# openSX70_ALADDIN_V397SEEED_20180210.net
KiCad netlist of a schematic drawn in EAGLE
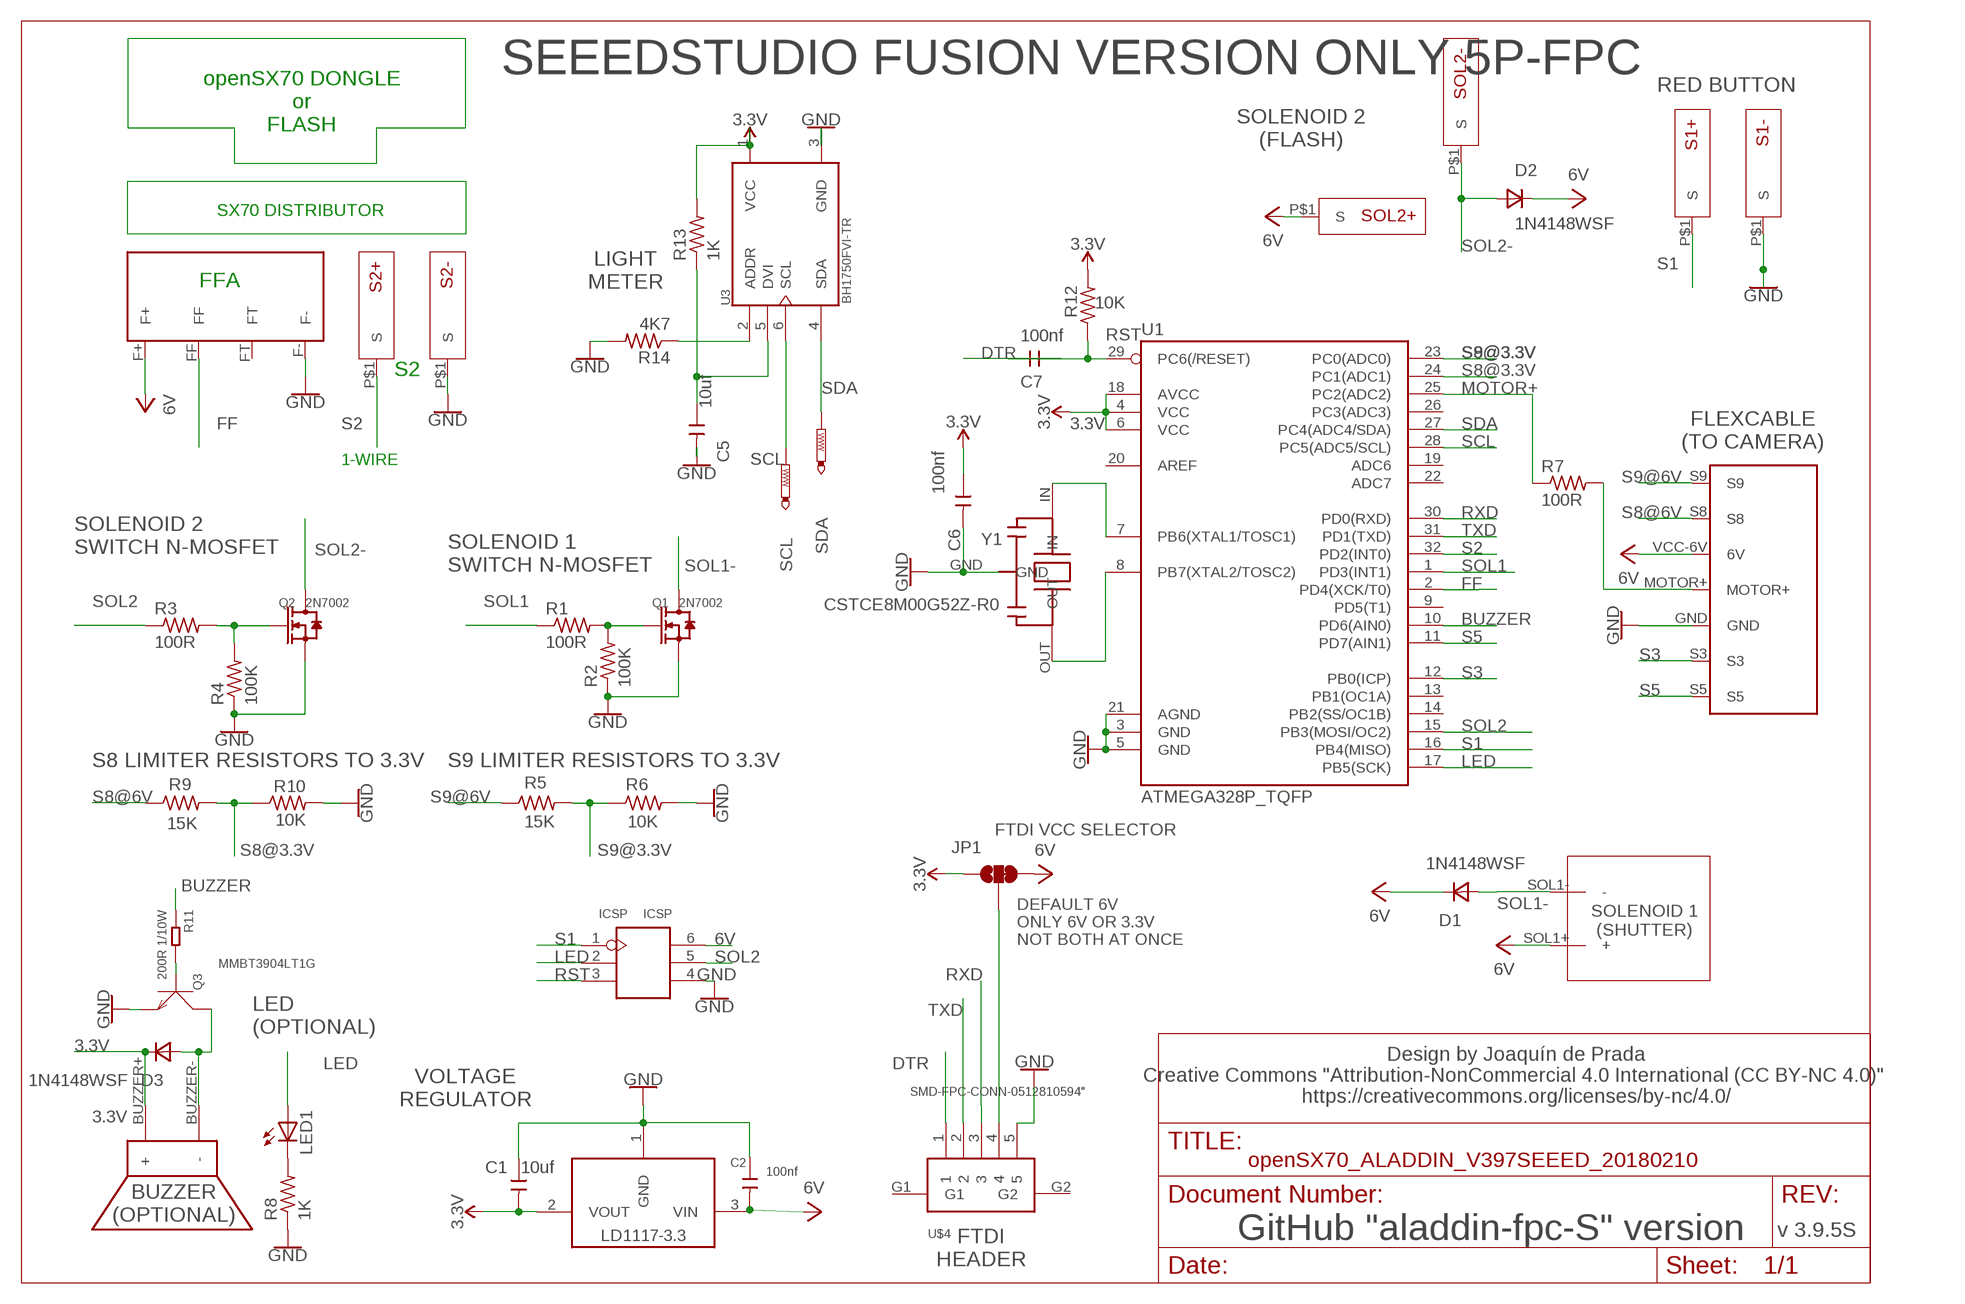
[diagram p0: schematic, sheet 1]

(export (version "E")
  (design (tool "Eeschema 10.0.6"))
  (components
    (comp (ref "C1")
      (value "10uf")
      (footprint "eagle-import:C0603")
      (fields (field (name "MPN") "CC0603KRX5R6BB106"))
      (libsource (lib "eagle-import") (part "CERAMIC-10UF-10V-10%-X5R(0603)"))
    )
    (comp (ref "C2")
      (value "100nf")
      (footprint "eagle-import:C0603")
      (fields (field (name "MPN") "CC0603KRX7R9BB104"))
      (libsource (lib "eagle-import") (part "CERAMIC-100NF-50V-10%-X7R(0603)"))
    )
    (comp (ref "C5")
      (value "10uf")
      (footprint "eagle-import:C0603")
      (fields (field (name "MPN") "CC0603KRX5R6BB106"))
      (libsource (lib "eagle-import") (part "CERAMIC-10UF-10V-10%-X5R(0603)"))
    )
    (comp (ref "C6")
      (value "100nf")
      (footprint "eagle-import:C0603")
      (fields (field (name "MPN") "CC0603KRX7R9BB104"))
      (libsource (lib "eagle-import") (part "CERAMIC-100NF-50V-10%-X7R(0603)"))
    )
    (comp (ref "C7")
      (value "100nf")
      (footprint "eagle-import:C0603")
      (fields (field (name "MPN") "CC0603KRX7R9BB104"))
      (libsource (lib "eagle-import") (part "CERAMIC-100NF-50V-10%-X7R(0603)"))
    )
    (comp (ref "D1")
      (value "1N4148WSF")
      (footprint "eagle-import:SOD323")
      (fields (field (name "MPN") "CDSOD323-T05C"))
      (libsource (lib "eagle-import") (part "DSOD323"))
    )
    (comp (ref "D2")
      (value "1N4148WSF")
      (footprint "eagle-import:SOD323")
      (fields (field (name "MPN") "CDSOD323-T05C"))
      (libsource (lib "eagle-import") (part "DSOD323"))
    )
    (comp (ref "D3")
      (value "1N4148WSF")
      (footprint "eagle-import:SOD323")
      (fields (field (name "MPN") "CDSOD323-T05C"))
      (libsource (lib "eagle-import") (part "DSOD323"))
    )
    (comp (ref "ICSP")
      (value "ICSP")
      (footprint "eagle-import:H2X3-2.54")
      (libsource (lib "eagle-import") (part "ICSP"))
    )
    (comp (ref "JP1")
      (value "FTDI VCC SELECTOR")
      (footprint "eagle-import:SMT-JUMPER_3_1-NC_TRACE_SILK")
      (libsource (lib "eagle-import") (part "JUMPER-SMT_3_1-NC_TRACE_SILK"))
    )
    (comp (ref "LD11172.5V")
      (value "LD1117 2.5V")
      (footprint "eagle-import:SOT223")
      (fields (field (name "MF") "Advanced Monolithic Systems") (field (name "MP") "AMS1117-5.0"))
      (libsource (lib "eagle-import") (part "LD1117-3.3"))
    )
    (comp (ref "LED1")
      (value "LEDCHIPLED_0805")
      (footprint "eagle-import:CHIPLED_0805")
      (libsource (lib "eagle-import") (part "LEDCHIPLED_0805"))
    )
    (comp (ref "Q1")
      (value "2N7002")
      (footprint "eagle-import:SOT-23")
      (fields (field (name "MPN") "2N7002,215"))
      (libsource (lib "eagle-import") (part "SMD-MOSFET-N-CH-60V-300MA-LOGIC-LEVEL-FET-2N7002(SOT-23)"))
    )
    (comp (ref "Q2")
      (value "2N7002")
      (footprint "eagle-import:SOT-23")
      (fields (field (name "MPN") "2N7002,215"))
      (libsource (lib "eagle-import") (part "SMD-MOSFET-N-CH-60V-300MA-LOGIC-LEVEL-FET-2N7002(SOT-23)"))
    )
    (comp (ref "Q3")
      (value "MMBT3904LT1G")
      (footprint "eagle-import:SOT-23")
      (libsource (lib "eagle-import") (part "SMD-TRANSISTORS-NPN-40V-200MA-MMBT3904LT1G(SOT-23)"))
    )
    (comp (ref "R1")
      (value "100R")
      (footprint "eagle-import:R0603")
      (libsource (lib "eagle-import") (part "R-US_R0603"))
    )
    (comp (ref "R2")
      (value "100K")
      (footprint "eagle-import:R0603")
      (libsource (lib "eagle-import") (part "R-US_R0603"))
    )
    (comp (ref "R3")
      (value "100R")
      (footprint "eagle-import:R0603")
      (libsource (lib "eagle-import") (part "R-US_R0603"))
    )
    (comp (ref "R4")
      (value "100K")
      (footprint "eagle-import:R0603")
      (libsource (lib "eagle-import") (part "R-US_R0603"))
    )
    (comp (ref "R5")
      (value "15K")
      (footprint "eagle-import:R0603")
      (libsource (lib "eagle-import") (part "R-US_R0603"))
    )
    (comp (ref "R6")
      (value "10K")
      (footprint "eagle-import:R0603")
      (libsource (lib "eagle-import") (part "R-US_R0603"))
    )
    (comp (ref "R7")
      (value "100R")
      (footprint "eagle-import:R0603")
      (libsource (lib "eagle-import") (part "R-US_R0603"))
    )
    (comp (ref "R8")
      (value "1K")
      (footprint "eagle-import:R0603")
      (libsource (lib "eagle-import") (part "R-US_R0603"))
    )
    (comp (ref "R9")
      (value "15K")
      (footprint "eagle-import:R0603")
      (libsource (lib "eagle-import") (part "R-US_R0603"))
    )
    (comp (ref "R10")
      (value "10K")
      (footprint "eagle-import:R0603")
      (libsource (lib "eagle-import") (part "R-US_R0603"))
    )
    (comp (ref "R11")
      (value "200R 1/10W")
      (footprint "eagle-import:R0603")
      (fields (field (name "MPN") "RC0603JR-07200RL"))
      (libsource (lib "eagle-import") (part "SMD-RES-200R-5%-1/10W(0603)"))
    )
    (comp (ref "R12")
      (value "10K")
      (footprint "eagle-import:R0603")
      (libsource (lib "eagle-import") (part "R-US_R0603"))
    )
    (comp (ref "R13")
      (value "1K")
      (footprint "eagle-import:R0603")
      (libsource (lib "eagle-import") (part "R-US_R0603"))
    )
    (comp (ref "R14")
      (value "4K7")
      (footprint "eagle-import:R0603")
      (libsource (lib "eagle-import") (part "R-US_R0603"))
    )
    (comp (ref "S1+")
      (value "SX70-S-PAD-NEW")
      (footprint "eagle-import:SX70-S-PAD2")
      (libsource (lib "eagle-import") (part "SX70-S-PAD-NEW"))
    )
    (comp (ref "S1-")
      (value "SX70-S-PAD-NEW")
      (footprint "eagle-import:SX70-S-PAD2")
      (libsource (lib "eagle-import") (part "SX70-S-PAD-NEW"))
    )
    (comp (ref "S2+")
      (value "SX70-S-PAD-NEW")
      (footprint "eagle-import:SX70-S-PAD2")
      (libsource (lib "eagle-import") (part "SX70-S-PAD-NEW"))
    )
    (comp (ref "S2-")
      (value "SX70-S-PAD-NEW")
      (footprint "eagle-import:SX70-S-PAD2")
      (libsource (lib "eagle-import") (part "SX70-S-PAD-NEW"))
    )
    (comp (ref "SCL")
      (value "PTR1TP08R")
      (footprint "eagle-import:TP08R")
      (libsource (lib "eagle-import") (part "PTR1TP08R"))
    )
    (comp (ref "SDA")
      (value "PTR1TP08R")
      (footprint "eagle-import:TP08R")
      (libsource (lib "eagle-import") (part "PTR1TP08R"))
    )
    (comp (ref "SOL1")
      (value "SX70-SOLENOID1-2PADS")
      (footprint "eagle-import:SX70-SOLENOID1-2")
      (libsource (lib "eagle-import") (part "SX70-SOLENOID1-2PADS"))
    )
    (comp (ref "SOL2+")
      (value "SX70-S-PAD-NEW")
      (footprint "eagle-import:SX70-S-PAD2")
      (libsource (lib "eagle-import") (part "SX70-S-PAD-NEW"))
    )
    (comp (ref "SOL2-")
      (value "SX70-S-PAD-NEW")
      (footprint "eagle-import:SX70-S-PAD2")
      (libsource (lib "eagle-import") (part "SX70-S-PAD-NEW"))
    )
    (comp (ref "U$1")
      (value "SX70-7-PAD")
      (footprint "eagle-import:SX70-7-PAD")
      (libsource (lib "eagle-import") (part "SX70-7-PAD"))
    )
    (comp (ref "U$2")
      (value "FFA")
      (footprint "eagle-import:FFA-PAD-PACKAGE")
      (libsource (lib "eagle-import") (part "SX70-FFA-PAD"))
    )
    (comp (ref "U$3")
      (value "CSET8-5G_V2")
      (footprint "eagle-import:CSET8-5G_PACKAGE")
      (libsource (lib "eagle-import") (part "CSET8-5G_V2"))
    )
    (comp (ref "U$4")
      (value "SMD-FPC-CONN-0512810594\"")
      (footprint "eagle-import:51281-0594")
      (libsource (lib "eagle-import") (part "SMD-FPC-CONN-0512810594{dblquote}"))
    )
    (comp (ref "U1")
      (value "ATMEGA328P_TQFP")
      (footprint "eagle-import:TQFP32-08")
      (libsource (lib "eagle-import") (part "ATMEGA328P_TQFP"))
    )
    (comp (ref "U3")
      (value "BH1750FVI-TR")
      (footprint "eagle-import:SOTFL50P300X75-6N")
      (fields (field (name "MF") "Rohm"))
      (libsource (lib "eagle-import") (part "BH1750FVI-TR"))
    )
    (comp (ref "Y1")
      (value "CSTCE8M00G52Z-R0")
      (footprint "eagle-import:CFP95P160X100-3N")
      (fields (field (name "MF") "Murata") (field (name "MP") "CSTCE16M0V53-R0"))
      (libsource (lib "eagle-import") (part "CSTCE16M0V53-R0"))
    )
  )
  (nets
    (net (code "1") (name "/BUZZER") (class "Default")
      (node (ref "R11") (pin "1") (pinfunction "1_1") (pintype "passive"))
      (node (ref "U1") (pin "10") (pinfunction "PD6(AIN0)_10") (pintype "bidirectional"))
    )
    (net (code "2") (name "/DTR") (class "Default")
      (node (ref "C7") (pin "1") (pinfunction "1_1") (pintype "passive"))
      (node (ref "U$4") (pin "1") (pinfunction "1_1") (pintype "bidirectional"))
    )
    (net (code "3") (name "/FF") (class "Default")
      (node (ref "U$2") (pin "FF") (pinfunction "FF_FF") (pintype "bidirectional"))
      (node (ref "U1") (pin "2") (pinfunction "PD4(XCK/T0)_2") (pintype "bidirectional"))
    )
    (net (code "4") (name "/LED") (class "Default")
      (node (ref "ICSP") (pin "2") (pinfunction "SCK_2") (pintype "bidirectional"))
      (node (ref "LED1") (pin "A") (pinfunction "A_A") (pintype "passive"))
      (node (ref "U1") (pin "17") (pinfunction "PB5(SCK)_17") (pintype "bidirectional"))
    )
    (net (code "5") (name "/MOTOR+") (class "Default")
      (node (ref "R7") (pin "1") (pinfunction "1_1") (pintype "passive"))
      (node (ref "U1") (pin "25") (pinfunction "PC2(ADC2)_25") (pintype "bidirectional"))
    )
    (net (code "6") (name "/RST") (class "Default")
      (node (ref "C7") (pin "2") (pinfunction "2_2") (pintype "passive"))
      (node (ref "ICSP") (pin "3") (pinfunction "RST_3") (pintype "bidirectional"))
      (node (ref "R12") (pin "1") (pinfunction "1_1") (pintype "passive"))
      (node (ref "U1") (pin "29") (pinfunction "PC6(/RESET)_29") (pintype "bidirectional"))
    )
    (net (code "7") (name "/RXD") (class "Default")
      (node (ref "U$4") (pin "3") (pinfunction "3_3") (pintype "bidirectional"))
      (node (ref "U1") (pin "30") (pinfunction "PD0(RXD)_30") (pintype "bidirectional"))
    )
    (net (code "8") (name "/S1") (class "Default")
      (node (ref "ICSP") (pin "1") (pinfunction "MISO_1") (pintype "bidirectional"))
      (node (ref "S1+") (pin "P$1") (pinfunction "S_P$1") (pintype "bidirectional"))
      (node (ref "U1") (pin "16") (pinfunction "PB4(MISO)_16") (pintype "bidirectional"))
    )
    (net (code "9") (name "/S2") (class "Default")
      (node (ref "S2+") (pin "P$1") (pinfunction "S_P$1") (pintype "bidirectional"))
      (node (ref "U1") (pin "32") (pinfunction "PD2(INT0)_32") (pintype "bidirectional"))
    )
    (net (code "10") (name "/S3") (class "Default")
      (node (ref "U$1") (pin "S3") (pinfunction "S3_S3") (pintype "bidirectional"))
      (node (ref "U1") (pin "12") (pinfunction "PB0(ICP)_12") (pintype "bidirectional"))
    )
    (net (code "11") (name "/S5") (class "Default")
      (node (ref "U$1") (pin "S5") (pinfunction "S5_S5") (pintype "bidirectional"))
      (node (ref "U1") (pin "11") (pinfunction "PD7(AIN1)_11") (pintype "bidirectional"))
    )
    (net (code "12") (name "/S8@3.3V") (class "Default")
      (node (ref "R10") (pin "1") (pinfunction "1_1") (pintype "passive"))
      (node (ref "R9") (pin "2") (pinfunction "2_2") (pintype "passive"))
      (node (ref "U1") (pin "24") (pinfunction "PC1(ADC1)_24") (pintype "bidirectional"))
    )
    (net (code "13") (name "/S8@6V") (class "Default")
      (node (ref "R9") (pin "1") (pinfunction "1_1") (pintype "passive"))
      (node (ref "U$1") (pin "S8") (pinfunction "S8_S8") (pintype "bidirectional"))
    )
    (net (code "14") (name "/S9@3.3V") (class "Default")
      (node (ref "R5") (pin "2") (pinfunction "2_2") (pintype "passive"))
      (node (ref "R6") (pin "1") (pinfunction "1_1") (pintype "passive"))
      (node (ref "U1") (pin "23") (pinfunction "PC0(ADC0)_23") (pintype "bidirectional"))
    )
    (net (code "15") (name "/S9@6V") (class "Default")
      (node (ref "R5") (pin "1") (pinfunction "1_1") (pintype "passive"))
      (node (ref "U$1") (pin "S9") (pinfunction "S9_S9") (pintype "bidirectional"))
    )
    (net (code "16") (name "/SCL") (class "Default")
      (node (ref "SCL") (pin "TP") (pinfunction "TP_TP") (pintype "input"))
      (node (ref "U1") (pin "28") (pinfunction "PC5(ADC5/SCL)_28") (pintype "bidirectional"))
      (node (ref "U3") (pin "6") (pinfunction "SCL_6") (pintype "input"))
    )
    (net (code "17") (name "/SDA") (class "Default")
      (node (ref "SDA") (pin "TP") (pinfunction "TP_TP") (pintype "input"))
      (node (ref "U1") (pin "27") (pinfunction "PC4(ADC4/SDA)_27") (pintype "bidirectional"))
      (node (ref "U3") (pin "4") (pinfunction "SDA_4") (pintype "bidirectional"))
    )
    (net (code "18") (name "/SOL1") (class "Default")
      (node (ref "R1") (pin "1") (pinfunction "1_1") (pintype "passive"))
      (node (ref "U1") (pin "1") (pinfunction "PD3(INT1)_1") (pintype "bidirectional"))
    )
    (net (code "19") (name "/SOL1-") (class "Default")
      (node (ref "D1") (pin "2") (pinfunction "A_2") (pintype "passive"))
      (node (ref "Q1") (pin "3") (pinfunction "D_3") (pintype "passive"))
      (node (ref "SOL1") (pin "SOL1-") (pinfunction "-_SOL1-") (pintype "bidirectional"))
    )
    (net (code "20") (name "/SOL2") (class "Default")
      (node (ref "ICSP") (pin "5") (pinfunction "MOSI_5") (pintype "bidirectional"))
      (node (ref "R3") (pin "1") (pinfunction "1_1") (pintype "passive"))
      (node (ref "U1") (pin "15") (pinfunction "PB3(MOSI/OC2)_15") (pintype "bidirectional"))
    )
    (net (code "21") (name "/SOL2-") (class "Default")
      (node (ref "D2") (pin "2") (pinfunction "A_2") (pintype "passive"))
      (node (ref "Q2") (pin "3") (pinfunction "D_3") (pintype "passive"))
      (node (ref "SOL2-") (pin "P$1") (pinfunction "S_P$1") (pintype "bidirectional"))
    )
    (net (code "22") (name "/TXD") (class "Default")
      (node (ref "U$4") (pin "2") (pinfunction "2_2") (pintype "bidirectional"))
      (node (ref "U1") (pin "31") (pinfunction "PD1(TXD)_31") (pintype "bidirectional"))
    )
    (net (code "23") (name "3.3V") (class "Default")
      (node (ref "C1") (pin "2") (pinfunction "2_2") (pintype "passive"))
      (node (ref "C6") (pin "1") (pinfunction "1_1") (pintype "passive"))
      (node (ref "D3") (pin "1") (pinfunction "C_1") (pintype "passive"))
      (node (ref "JP1") (pin "1") (pinfunction "1_1") (pintype "passive"))
      (node (ref "LD11172.5V") (pin "2") (pinfunction "VOUT_2") (pintype "bidirectional"))
      (node (ref "R12") (pin "2") (pinfunction "2_2") (pintype "passive"))
      (node (ref "R13") (pin "2") (pinfunction "2_2") (pintype "passive"))
      (node (ref "U$3") (pin "BUZZER+") (pinfunction "+_BUZZER+") (pintype "bidirectional"))
      (node (ref "U1") (pin "18") (pinfunction "AVCC_18") (pintype "bidirectional"))
      (node (ref "U1") (pin "4") (pinfunction "VCC_4") (pintype "bidirectional"))
      (node (ref "U1") (pin "6") (pinfunction "VCC_6") (pintype "bidirectional"))
      (node (ref "U3") (pin "1") (pinfunction "VCC_1") (pintype "power_in"))
    )
    (net (code "24") (name "6V") (class "Default")
      (node (ref "C2") (pin "2") (pinfunction "2_2") (pintype "passive"))
      (node (ref "D1") (pin "1") (pinfunction "C_1") (pintype "passive"))
      (node (ref "D2") (pin "1") (pinfunction "C_1") (pintype "passive"))
      (node (ref "ICSP") (pin "6") (pinfunction "VCC_6") (pintype "bidirectional"))
      (node (ref "JP1") (pin "3") (pinfunction "3_3") (pintype "passive"))
      (node (ref "LD11172.5V") (pin "3") (pinfunction "VIN_3") (pintype "bidirectional"))
      (node (ref "SOL1") (pin "SOL1+") (pinfunction "+_SOL1+") (pintype "bidirectional"))
      (node (ref "SOL2+") (pin "P$1") (pinfunction "S_P$1") (pintype "bidirectional"))
      (node (ref "U$1") (pin "VCC-6V") (pinfunction "6V_VCC-6V") (pintype "bidirectional"))
      (node (ref "U$2") (pin "F+") (pinfunction "F+_F+") (pintype "bidirectional"))
    )
    (net (code "25") (name "GND") (class "Default")
      (node (ref "C1") (pin "1") (pinfunction "1_1") (pintype "passive"))
      (node (ref "C2") (pin "1") (pinfunction "1_1") (pintype "passive"))
      (node (ref "C5") (pin "2") (pinfunction "2_2") (pintype "passive"))
      (node (ref "C6") (pin "2") (pinfunction "2_2") (pintype "passive"))
      (node (ref "ICSP") (pin "4") (pinfunction "GND_4") (pintype "bidirectional"))
      (node (ref "LD11172.5V") (pin "1") (pinfunction "GND_1") (pintype "bidirectional"))
      (node (ref "Q1") (pin "2") (pinfunction "S_2") (pintype "passive"))
      (node (ref "Q2") (pin "2") (pinfunction "S_2") (pintype "passive"))
      (node (ref "Q3") (pin "2") (pinfunction "E_2") (pintype "passive"))
      (node (ref "R10") (pin "2") (pinfunction "2_2") (pintype "passive"))
      (node (ref "R14") (pin "2") (pinfunction "2_2") (pintype "passive"))
      (node (ref "R2") (pin "1") (pinfunction "1_1") (pintype "passive"))
      (node (ref "R4") (pin "1") (pinfunction "1_1") (pintype "passive"))
      (node (ref "R6") (pin "2") (pinfunction "2_2") (pintype "passive"))
      (node (ref "R8") (pin "1") (pinfunction "1_1") (pintype "passive"))
      (node (ref "S1-") (pin "P$1") (pinfunction "S_P$1") (pintype "bidirectional"))
      (node (ref "S2-") (pin "P$1") (pinfunction "S_P$1") (pintype "bidirectional"))
      (node (ref "U$1") (pin "GND") (pinfunction "GND_GND") (pintype "bidirectional"))
      (node (ref "U$2") (pin "F-") (pinfunction "F-_F-") (pintype "bidirectional"))
      (node (ref "U$4") (pin "5") (pinfunction "5_5") (pintype "bidirectional"))
      (node (ref "U1") (pin "21") (pinfunction "AGND_21") (pintype "bidirectional"))
      (node (ref "U1") (pin "3") (pinfunction "GND_3") (pintype "bidirectional"))
      (node (ref "U1") (pin "5") (pinfunction "GND_5") (pintype "bidirectional"))
      (node (ref "U3") (pin "3") (pinfunction "GND_3") (pintype "power_in"))
      (node (ref "Y1") (pin "GND") (pinfunction "GND_GND") (pintype "passive"))
    )
    (net (code "26") (name "Net-(D3-A)") (class "Default")
      (node (ref "D3") (pin "2") (pinfunction "A_2") (pintype "passive"))
      (node (ref "Q3") (pin "3") (pinfunction "C_3") (pintype "passive"))
      (node (ref "U$3") (pin "BUZZER-") (pinfunction "-_BUZZER-") (pintype "bidirectional"))
    )
    (net (code "27") (name "Net-(JP1-Pad2)") (class "Default")
      (node (ref "JP1") (pin "2") (pinfunction "2_2") (pintype "passive"))
      (node (ref "U$4") (pin "4") (pinfunction "4_4") (pintype "bidirectional"))
    )
    (net (code "28") (name "Net-(LED1-PadC)") (class "Default")
      (node (ref "LED1") (pin "C") (pinfunction "C_C") (pintype "passive"))
      (node (ref "R8") (pin "2") (pinfunction "2_2") (pintype "passive"))
    )
    (net (code "29") (name "Net-(Q1-G)") (class "Default")
      (node (ref "Q1") (pin "1") (pinfunction "G_1") (pintype "passive"))
      (node (ref "R1") (pin "2") (pinfunction "2_2") (pintype "passive"))
      (node (ref "R2") (pin "2") (pinfunction "2_2") (pintype "passive"))
    )
    (net (code "30") (name "Net-(Q2-G)") (class "Default")
      (node (ref "Q2") (pin "1") (pinfunction "G_1") (pintype "passive"))
      (node (ref "R3") (pin "2") (pinfunction "2_2") (pintype "passive"))
      (node (ref "R4") (pin "2") (pinfunction "2_2") (pintype "passive"))
    )
    (net (code "31") (name "Net-(Q3-B)") (class "Default")
      (node (ref "Q3") (pin "1") (pinfunction "B_1") (pintype "passive"))
      (node (ref "R11") (pin "2") (pinfunction "2_2") (pintype "passive"))
    )
    (net (code "32") (name "Net-(R7-Pad2)") (class "Default")
      (node (ref "R7") (pin "2") (pinfunction "2_2") (pintype "passive"))
      (node (ref "U$1") (pin "MOTOR+") (pinfunction "MOTOR+_MOTOR+") (pintype "bidirectional"))
    )
    (net (code "33") (name "Net-(U1-PB6(XTAL1{slash}TOSC1))") (class "Default")
      (node (ref "U1") (pin "7") (pinfunction "PB6(XTAL1/TOSC1)_7") (pintype "bidirectional"))
      (node (ref "Y1") (pin "IN") (pinfunction "IN_IN") (pintype "input"))
    )
    (net (code "34") (name "Net-(U1-PB7(XTAL2{slash}TOSC2))") (class "Default")
      (node (ref "U1") (pin "8") (pinfunction "PB7(XTAL2/TOSC2)_8") (pintype "bidirectional"))
      (node (ref "Y1") (pin "OUT") (pinfunction "OUT_OUT") (pintype "output"))
    )
    (net (code "35") (name "Net-(U3-ADDR)") (class "Default")
      (node (ref "R14") (pin "1") (pinfunction "1_1") (pintype "passive"))
      (node (ref "U3") (pin "2") (pinfunction "ADDR_2") (pintype "input"))
    )
    (net (code "36") (name "Net-(U3-DVI)") (class "Default")
      (node (ref "C5") (pin "1") (pinfunction "1_1") (pintype "passive"))
      (node (ref "R13") (pin "1") (pinfunction "1_1") (pintype "passive"))
      (node (ref "U3") (pin "5") (pinfunction "DVI_5") (pintype "input"))
    )
    (net (code "37") (name "unconnected-(U$2-PadFT)") (class "Default")
      (node (ref "U$2") (pin "FT") (pinfunction "FT_FT") (pintype "bidirectional"))
    )
    (net (code "38") (name "unconnected-(U$4-PadG1)") (class "Default")
      (node (ref "U$4") (pin "G1") (pinfunction "G1_G1") (pintype "bidirectional"))
    )
    (net (code "39") (name "unconnected-(U$4-PadG2)") (class "Default")
      (node (ref "U$4") (pin "G2") (pinfunction "G2_G2") (pintype "bidirectional"))
    )
    (net (code "40") (name "unconnected-(U1-ADC6-Pad19)") (class "Default")
      (node (ref "U1") (pin "19") (pinfunction "ADC6_19") (pintype "bidirectional"))
    )
    (net (code "41") (name "unconnected-(U1-ADC7-Pad22)") (class "Default")
      (node (ref "U1") (pin "22") (pinfunction "ADC7_22") (pintype "bidirectional"))
    )
    (net (code "42") (name "unconnected-(U1-AREF-Pad20)") (class "Default")
      (node (ref "U1") (pin "20") (pinfunction "AREF_20") (pintype "bidirectional"))
    )
    (net (code "43") (name "unconnected-(U1-PB1(OC1A)-Pad13)") (class "Default")
      (node (ref "U1") (pin "13") (pinfunction "PB1(OC1A)_13") (pintype "bidirectional"))
    )
    (net (code "44") (name "unconnected-(U1-PB2(SS{slash}OC1B)-Pad14)") (class "Default")
      (node (ref "U1") (pin "14") (pinfunction "PB2(SS/OC1B)_14") (pintype "bidirectional"))
    )
    (net (code "45") (name "unconnected-(U1-PC3(ADC3)-Pad26)") (class "Default")
      (node (ref "U1") (pin "26") (pinfunction "PC3(ADC3)_26") (pintype "bidirectional"))
    )
    (net (code "46") (name "unconnected-(U1-PD5(T1)-Pad9)") (class "Default")
      (node (ref "U1") (pin "9") (pinfunction "PD5(T1)_9") (pintype "bidirectional"))
    )
  )
)
